# power_electronicsV4_1.net
KiCad netlist of a schematic drawn in EAGLE
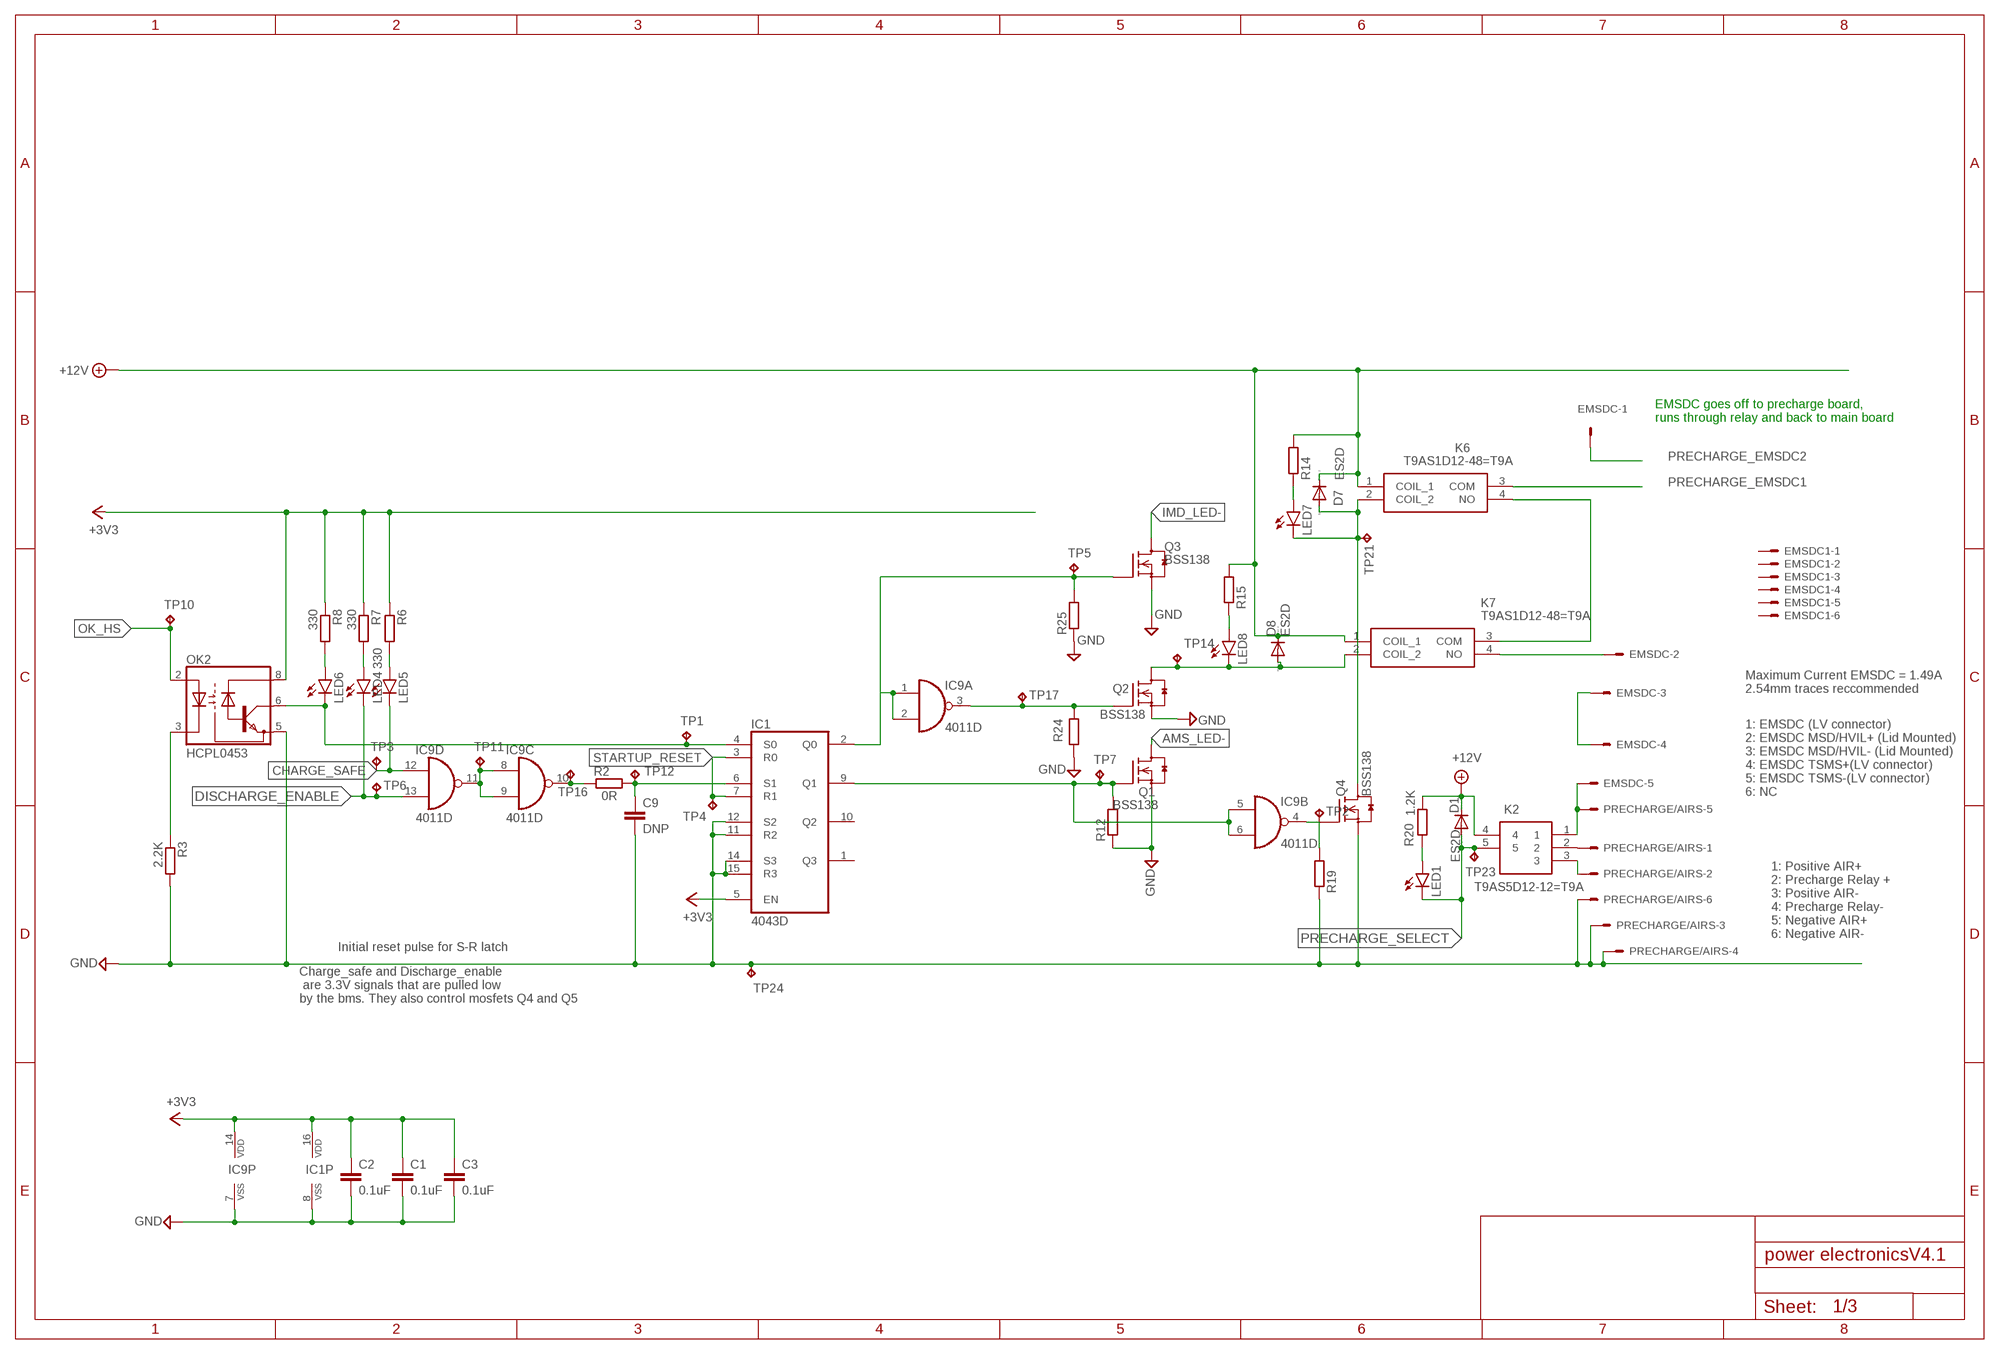
[diagram p0: schematic, sheet 1]
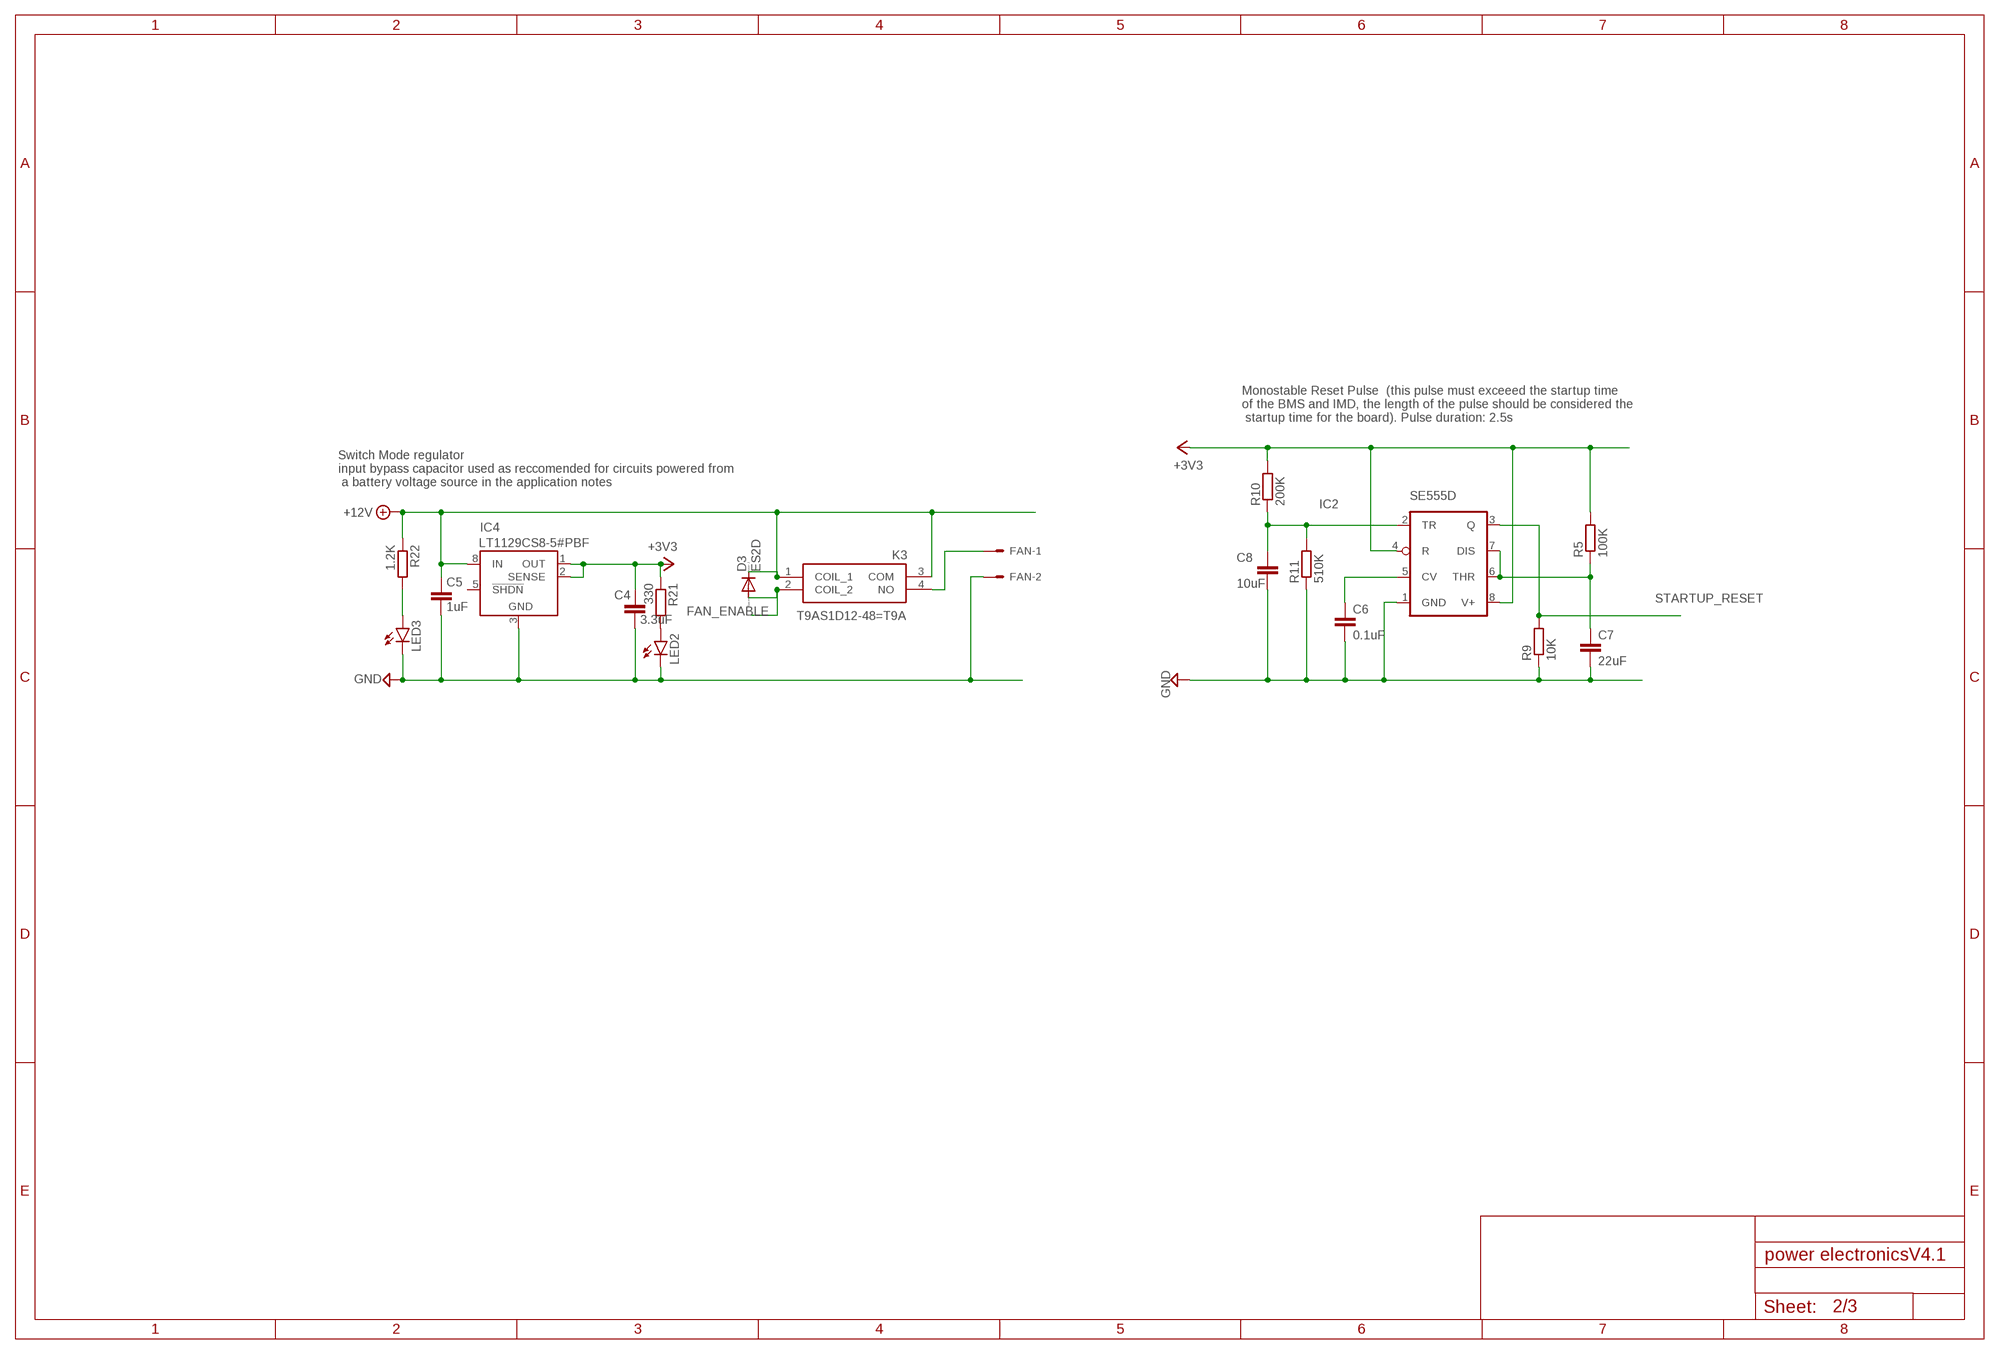
[diagram p1: schematic, sheet 2]
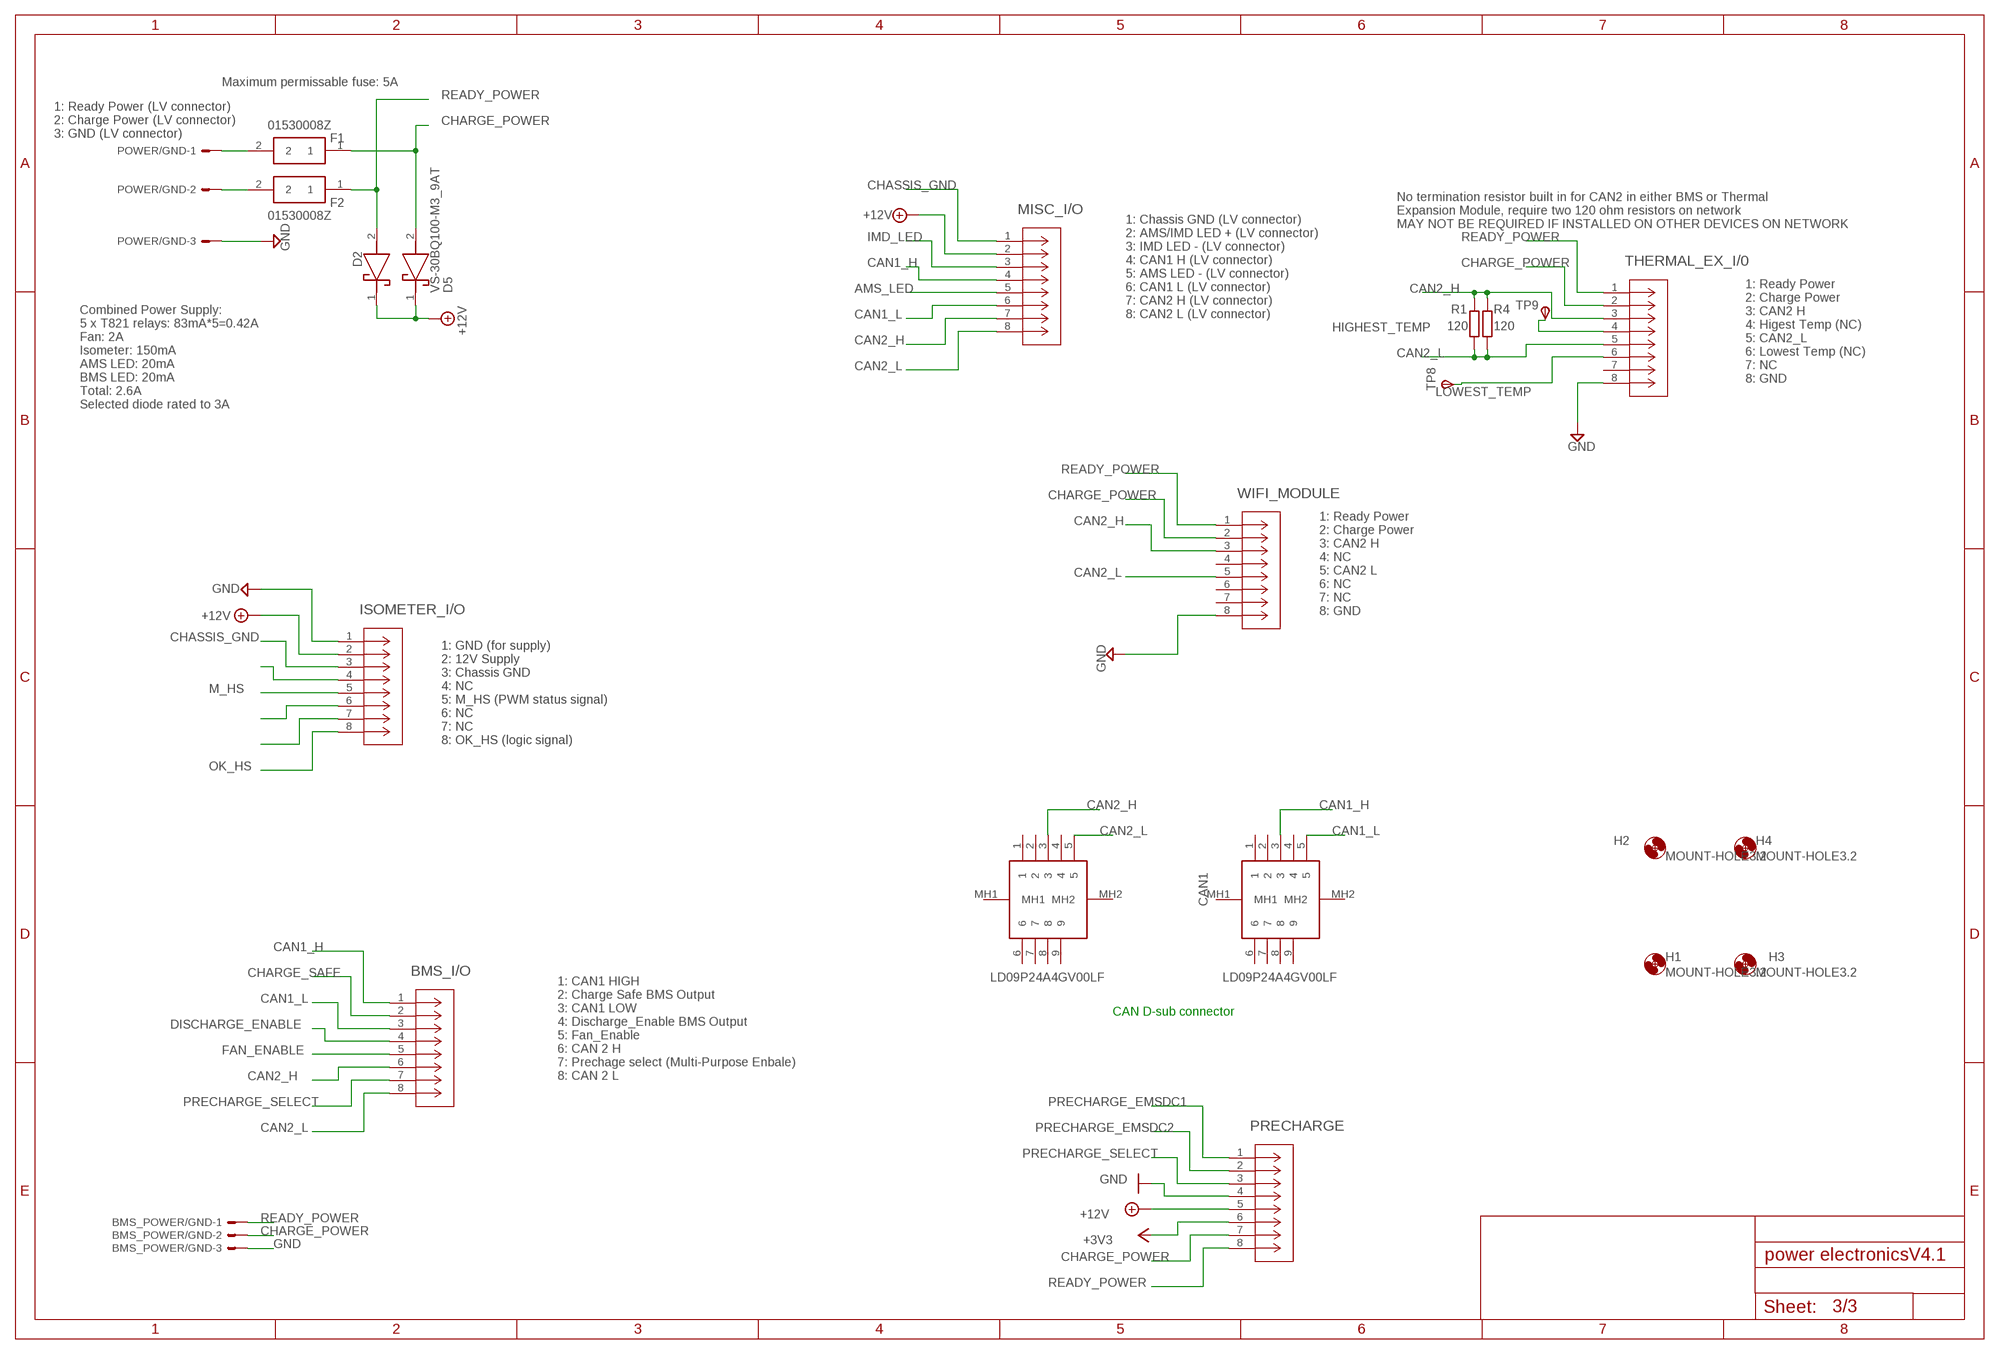
[diagram p2: schematic, sheet 3]

(export (version "E")
  (design (tool "Eeschema 10.0.6"))
  (components
    (comp (ref "BMS_I/O")
      (value "MINI-SPOX_22035085")
      (footprint "eagle-import:CON_22035085_MOL")
      (fields
        (field (name "MANUFACTURER_PART_NUMBER") "22035085")
        (field (name "COPYRIGHT") "Copyright (C) 2023 Ultra Librarian. All rights reserved.")
      )
      (libsource (lib "eagle-import") (part "MINI-SPOX_22035085"))
    )
    (comp (ref "BMS_POWER/GND")
      (value "KK-156-3")
      (footprint "eagle-import:KK-156-3")
      (fields (field (name "MF") "MOLEX"))
      (libsource (lib "eagle-import") (part "KK-156-3"))
    )
    (comp (ref "CAN1")
      (value "LD09P24A4GV00LF")
      (footprint "eagle-import:LD09P24A4GV00LF")
      (fields (field (name "MOUSER_PART_NUMBER") "649-LD09P24A4GV00LF"))
      (libsource (lib "eagle-import") (part "LD09P24A4GV00LF"))
    )
    (comp (ref "CAN2")
      (value "LD09P24A4GV00LF")
      (footprint "eagle-import:LD09P24A4GV00LF")
      (fields (field (name "MOUSER_PART_NUMBER") "649-LD09P24A4GV00LF"))
      (libsource (lib "eagle-import") (part "LD09P24A4GV00LF"))
    )
    (comp (ref "D2")
      (value "VS-30BQ100-M3_9AT")
      (footprint "eagle-import:DIOM7959X262N")
      (fields
        (field (name "MANUFACTURER_PART_NUMBER") "VS-30BQ100-M3/9AT")
        (field (name "MOUSER_PART_NUMBER") "78-VS-30BQ100-M39AT")
      )
      (libsource (lib "eagle-import") (part "VS-30BQ100-M3_9AT"))
    )
    (comp (ref "D5")
      (value "VS-30BQ100-M3_9AT")
      (footprint "eagle-import:DIOM7959X262N")
      (fields
        (field (name "MANUFACTURER_PART_NUMBER") "VS-30BQ100-M3/9AT")
        (field (name "MOUSER_PART_NUMBER") "78-VS-30BQ100-M39AT")
      )
      (libsource (lib "eagle-import") (part "VS-30BQ100-M3_9AT"))
    )
    (comp (ref "F1")
      (value "01530008Z")
      (footprint "eagle-import:01530008")
      (fields (field (name "RS_PART_NUMBER") "3607317"))
      (libsource (lib "eagle-import") (part "01530008Z"))
    )
    (comp (ref "F2")
      (value "01530008Z")
      (footprint "eagle-import:01530008")
      (fields (field (name "RS_PART_NUMBER") "3607317"))
      (libsource (lib "eagle-import") (part "01530008Z"))
    )
    (comp (ref "H1")
      (value "MOUNT-HOLE3.2")
      (footprint "eagle-import:3,2")
      (libsource (lib "eagle-import") (part "MOUNT-HOLE3.2"))
    )
    (comp (ref "H2")
      (value "MOUNT-HOLE3.2")
      (footprint "eagle-import:3,2")
      (libsource (lib "eagle-import") (part "MOUNT-HOLE3.2"))
    )
    (comp (ref "H3")
      (value "MOUNT-HOLE3.2")
      (footprint "eagle-import:3,2")
      (libsource (lib "eagle-import") (part "MOUNT-HOLE3.2"))
    )
    (comp (ref "H4")
      (value "MOUNT-HOLE3.2")
      (footprint "eagle-import:3,2")
      (libsource (lib "eagle-import") (part "MOUNT-HOLE3.2"))
    )
    (comp (ref "ISOMETER_I/O")
      (value "MINI-SPOX_22035085")
      (footprint "eagle-import:CON_22035085_MOL")
      (fields
        (field (name "MANUFACTURER_PART_NUMBER") "22035085")
        (field (name "COPYRIGHT") "Copyright (C) 2023 Ultra Librarian. All rights reserved.")
      )
      (libsource (lib "eagle-import") (part "MINI-SPOX_22035085"))
    )
    (comp (ref "MISC_I/O")
      (value "MINI-SPOX_22035085")
      (footprint "eagle-import:CON_22035085_MOL")
      (fields
        (field (name "MANUFACTURER_PART_NUMBER") "22035085")
        (field (name "COPYRIGHT") "Copyright (C) 2023 Ultra Librarian. All rights reserved.")
      )
      (libsource (lib "eagle-import") (part "MINI-SPOX_22035085"))
    )
    (comp (ref "POWER/GND")
      (value "KK-156-3")
      (footprint "eagle-import:KK-156-3")
      (fields (field (name "MF") "MOLEX"))
      (libsource (lib "eagle-import") (part "KK-156-3"))
    )
    (comp (ref "PRECHARGE")
      (value "MINI-SPOX_22035085")
      (footprint "eagle-import:CON_22035085_MOL")
      (fields
        (field (name "MANUFACTURER_PART_NUMBER") "22035085")
        (field (name "COPYRIGHT") "Copyright (C) 2023 Ultra Librarian. All rights reserved.")
      )
      (libsource (lib "eagle-import") (part "MINI-SPOX_22035085"))
    )
    (comp (ref "R1")
      (value "120")
      (footprint "eagle-import:R1206")
      (libsource (lib "eagle-import") (part "R-EU_R1206"))
    )
    (comp (ref "R4")
      (value "120")
      (footprint "eagle-import:R1206")
      (libsource (lib "eagle-import") (part "R-EU_R1206"))
    )
    (comp (ref "THERMAL_EX_I/0")
      (value "MINI-SPOX_22035085")
      (footprint "eagle-import:CON_22035085_MOL")
      (fields
        (field (name "MANUFACTURER_PART_NUMBER") "22035085")
        (field (name "COPYRIGHT") "Copyright (C) 2023 Ultra Librarian. All rights reserved.")
      )
      (libsource (lib "eagle-import") (part "MINI-SPOX_22035085"))
    )
    (comp (ref "TP8")
      (value "TPSTP11R")
      (footprint "eagle-import:TP11R")
      (libsource (lib "eagle-import") (part "TPSTP11R"))
    )
    (comp (ref "TP9")
      (value "TPSTP11R")
      (footprint "eagle-import:TP11R")
      (libsource (lib "eagle-import") (part "TPSTP11R"))
    )
    (comp (ref "WIFI_MODULE")
      (value "MINI-SPOX_22035085")
      (footprint "eagle-import:CON_22035085_MOL")
      (fields
        (field (name "MANUFACTURER_PART_NUMBER") "22035085")
        (field (name "COPYRIGHT") "Copyright (C) 2023 Ultra Librarian. All rights reserved.")
      )
      (libsource (lib "eagle-import") (part "MINI-SPOX_22035085"))
    )
    (comp (ref "C4")
      (value "3.3uF")
      (footprint "eagle-import:C0805")
      (libsource (lib "eagle-import") (part "C-EUC0805"))
    )
    (comp (ref "C5")
      (value "1uF")
      (footprint "eagle-import:C0805")
      (libsource (lib "eagle-import") (part "C-EUC0805"))
    )
    (comp (ref "C6")
      (value "0.1uF")
      (footprint "eagle-import:C0805")
      (libsource (lib "eagle-import") (part "C-EUC0805"))
    )
    (comp (ref "C7")
      (value "22uF")
      (footprint "eagle-import:C1206")
      (libsource (lib "eagle-import") (part "C-EUC1206"))
    )
    (comp (ref "C8")
      (value "10uF")
      (footprint "eagle-import:C0805")
      (libsource (lib "eagle-import") (part "C-EUC0805"))
    )
    (comp (ref "D3")
      (value "ES2D")
      (footprint "eagle-import:SMB")
      (libsource (lib "eagle-import") (part "ES2D"))
    )
    (comp (ref "FAN")
      (value "KK-156-2")
      (footprint "eagle-import:KK-156-2")
      (fields (field (name "MF") "MOLEX"))
      (libsource (lib "eagle-import") (part "KK-156-2"))
    )
    (comp (ref "IC2")
      (value "SE555D")
      (footprint "eagle-import:SO08")
      (libsource (lib "eagle-import") (part "555DSE"))
    )
    (comp (ref "IC4")
      (value "LT1129CS8")
      (footprint "eagle-import:SOIC8")
      (fields (field (name "MPN") "LT1129CS8-5#PBF"))
      (libsource (lib "eagle-import") (part "LT1129CS8"))
    )
    (comp (ref "K3")
      (value "T9AS1D12-48=T9A")
      (footprint "eagle-import:T9AS1D1248T9A")
      (fields (field (name "RS_PART_NUMBER") "6802534P"))
      (libsource (lib "eagle-import") (part "T9AS1D12-48=T9A"))
    )
    (comp (ref "LED2")
      (value "LEDSML0805")
      (footprint "eagle-import:SML0805")
      (libsource (lib "eagle-import") (part "LEDSML0805"))
    )
    (comp (ref "LED3")
      (value "LEDSML0805")
      (footprint "eagle-import:SML0805")
      (libsource (lib "eagle-import") (part "LEDSML0805"))
    )
    (comp (ref "R5")
      (value "100K")
      (footprint "eagle-import:R0805")
      (libsource (lib "eagle-import") (part "R-EU_R0805"))
    )
    (comp (ref "R9")
      (value "10K")
      (footprint "eagle-import:R0805")
      (libsource (lib "eagle-import") (part "R-EU_R0805"))
    )
    (comp (ref "R10")
      (value "200K")
      (footprint "eagle-import:R0805")
      (libsource (lib "eagle-import") (part "R-EU_R0805"))
    )
    (comp (ref "R11")
      (value "510K")
      (footprint "eagle-import:R0805")
      (libsource (lib "eagle-import") (part "R-EU_R0805"))
    )
    (comp (ref "R21")
      (value "330")
      (footprint "eagle-import:R0805")
      (libsource (lib "eagle-import") (part "R-EU_R0805"))
    )
    (comp (ref "R22")
      (value "1.2K")
      (footprint "eagle-import:R0805")
      (libsource (lib "eagle-import") (part "R-EU_R0805"))
    )
    (comp (ref "C1")
      (value "0.1uF")
      (footprint "eagle-import:C0805")
      (libsource (lib "eagle-import") (part "C-EUC0805"))
    )
    (comp (ref "C2")
      (value "0.1uF")
      (footprint "eagle-import:C0805")
      (libsource (lib "eagle-import") (part "C-EUC0805"))
    )
    (comp (ref "C3")
      (value "0.1uF")
      (footprint "eagle-import:C0805")
      (libsource (lib "eagle-import") (part "C-EUC0805"))
    )
    (comp (ref "C9")
      (value "DNP")
      (footprint "eagle-import:C0805K")
      (libsource (lib "eagle-import") (part "C-EUC0805K"))
    )
    (comp (ref "D1")
      (value "ES2D")
      (footprint "eagle-import:SMB")
      (libsource (lib "eagle-import") (part "ES2D"))
    )
    (comp (ref "D7")
      (value "ES2D")
      (footprint "eagle-import:SMB")
      (libsource (lib "eagle-import") (part "ES2D"))
    )
    (comp (ref "D8")
      (value "ES2D")
      (footprint "eagle-import:SMB")
      (libsource (lib "eagle-import") (part "ES2D"))
    )
    (comp (ref "EMSDC")
      (value "KK-156-6")
      (footprint "eagle-import:KK-156-6")
      (fields (field (name "MF") "MOLEX"))
      (libsource (lib "eagle-import") (part "KK-156-6"))
    )
    (comp (ref "EMSDC1")
      (value "KK-156-6")
      (footprint "eagle-import:KK-156-6")
      (fields (field (name "MF") "MOLEX"))
      (libsource (lib "eagle-import") (part "KK-156-6"))
    )
    (comp (ref "IC1")
      (value "4043D")
      (footprint "eagle-import:SO16")
      (libsource (lib "eagle-import") (part "4043D"))
    )
    (comp (ref "IC9")
      (value "4011D")
      (footprint "eagle-import:SO14")
      (libsource (lib "eagle-import") (part "4011D"))
    )
    (comp (ref "K2")
      (value "T9AS5D12-12=T9A")
      (footprint "eagle-import:T9AS1D12")
      (fields (field (name "RS_PART_NUMBER") "6802528"))
      (libsource (lib "eagle-import") (part "T9AS5D12-12=T9A"))
    )
    (comp (ref "K6")
      (value "T9AS1D12-48=T9A")
      (footprint "eagle-import:T9AS1D1248T9A")
      (libsource (lib "eagle-import") (part "T9AS1D12-12=T9A_T9AS1D12-48=T9A"))
    )
    (comp (ref "K7")
      (value "T9AS1D12-48=T9A")
      (footprint "eagle-import:T9AS1D1248T9A")
      (libsource (lib "eagle-import") (part "T9AS1D12-12=T9A_T9AS1D12-48=T9A"))
    )
    (comp (ref "LED1")
      (value "LEDSML0805")
      (footprint "eagle-import:SML0805")
      (libsource (lib "eagle-import") (part "LEDSML0805"))
    )
    (comp (ref "LED4")
      (value "LEDSML0805")
      (footprint "eagle-import:SML0805")
      (libsource (lib "eagle-import") (part "LEDSML0805"))
    )
    (comp (ref "LED5")
      (value "LEDSML0805")
      (footprint "eagle-import:SML0805")
      (libsource (lib "eagle-import") (part "LEDSML0805"))
    )
    (comp (ref "LED6")
      (value "LEDSML0805")
      (footprint "eagle-import:SML0805")
      (libsource (lib "eagle-import") (part "LEDSML0805"))
    )
    (comp (ref "LED7")
      (value "LEDSML0805")
      (footprint "eagle-import:SML0805")
      (libsource (lib "eagle-import") (part "LEDSML0805"))
    )
    (comp (ref "LED8")
      (value "LEDSML0805")
      (footprint "eagle-import:SML0805")
      (libsource (lib "eagle-import") (part "LEDSML0805"))
    )
    (comp (ref "OK2")
      (value "HCPL0453")
      (footprint "eagle-import:SOIC08")
      (fields (field (name "MF") "AGILENT TECHNOLOGIES") (field (name "MPN") "HCPL-0453-000E"))
      (libsource (lib "eagle-import") (part "HCPL0453"))
    )
    (comp (ref "PRECHARGE/AIRS")
      (value "KK-156-6")
      (footprint "eagle-import:KK-156-6")
      (fields (field (name "MF") "MOLEX"))
      (libsource (lib "eagle-import") (part "KK-156-6"))
    )
    (comp (ref "Q1")
      (value "BSS138")
      (footprint "eagle-import:SOT23")
      (libsource (lib "eagle-import") (part "BSS138"))
    )
    (comp (ref "Q2")
      (value "BSS138")
      (footprint "eagle-import:SOT23")
      (libsource (lib "eagle-import") (part "BSS138"))
    )
    (comp (ref "Q3")
      (value "BSS138")
      (footprint "eagle-import:SOT23")
      (libsource (lib "eagle-import") (part "BSS138"))
    )
    (comp (ref "Q4")
      (value "BSS138")
      (footprint "eagle-import:SOT23")
      (libsource (lib "eagle-import") (part "BSS138"))
    )
    (comp (ref "R2")
      (value "0R")
      (footprint "eagle-import:R0805")
      (libsource (lib "eagle-import") (part "R-EU_R0805"))
    )
    (comp (ref "R3")
      (value "2.2K")
      (footprint "eagle-import:R0805")
      (libsource (lib "eagle-import") (part "R-EU_R0805"))
    )
    (comp (ref "R6")
      (value "330")
      (footprint "eagle-import:R0805")
      (libsource (lib "eagle-import") (part "R-EU_R0805"))
    )
    (comp (ref "R7")
      (value "330")
      (footprint "eagle-import:R0805")
      (libsource (lib "eagle-import") (part "R-EU_R0805"))
    )
    (comp (ref "R8")
      (value "330")
      (footprint "eagle-import:R0805")
      (libsource (lib "eagle-import") (part "R-EU_R0805"))
    )
    (comp (ref "R12")
      (value "R-EU_R0805")
      (footprint "eagle-import:R0805")
      (libsource (lib "eagle-import") (part "R-EU_R0805"))
    )
    (comp (ref "R14")
      (value "R-EU_R0805")
      (footprint "eagle-import:R0805")
      (libsource (lib "eagle-import") (part "R-EU_R0805"))
    )
    (comp (ref "R15")
      (value "R-EU_R0805")
      (footprint "eagle-import:R0805")
      (libsource (lib "eagle-import") (part "R-EU_R0805"))
    )
    (comp (ref "R19")
      (value "R-EU_R0805")
      (footprint "eagle-import:R0805")
      (libsource (lib "eagle-import") (part "R-EU_R0805"))
    )
    (comp (ref "R20")
      (value "1.2K")
      (footprint "eagle-import:R0805")
      (libsource (lib "eagle-import") (part "R-EU_R0805"))
    )
    (comp (ref "R24")
      (value "R-EU_R0805")
      (footprint "eagle-import:R0805")
      (libsource (lib "eagle-import") (part "R-EU_R0805"))
    )
    (comp (ref "R25")
      (value "R-EU_R0805")
      (footprint "eagle-import:R0805")
      (libsource (lib "eagle-import") (part "R-EU_R0805"))
    )
    (comp (ref "TP1")
      (value "TPPAD1-17")
      (footprint "eagle-import:P1-17")
      (libsource (lib "eagle-import") (part "TPPAD1-17"))
    )
    (comp (ref "TP2")
      (value "TPPAD1-17")
      (footprint "eagle-import:P1-17")
      (libsource (lib "eagle-import") (part "TPPAD1-17"))
    )
    (comp (ref "TP3")
      (value "TPPAD1-17")
      (footprint "eagle-import:P1-17")
      (libsource (lib "eagle-import") (part "TPPAD1-17"))
    )
    (comp (ref "TP4")
      (value "TPPAD1-17")
      (footprint "eagle-import:P1-17")
      (libsource (lib "eagle-import") (part "TPPAD1-17"))
    )
    (comp (ref "TP5")
      (value "TPPAD1-17")
      (footprint "eagle-import:P1-17")
      (libsource (lib "eagle-import") (part "TPPAD1-17"))
    )
    (comp (ref "TP6")
      (value "TPPAD1-17")
      (footprint "eagle-import:P1-17")
      (libsource (lib "eagle-import") (part "TPPAD1-17"))
    )
    (comp (ref "TP7")
      (value "TPPAD1-17")
      (footprint "eagle-import:P1-17")
      (libsource (lib "eagle-import") (part "TPPAD1-17"))
    )
    (comp (ref "TP10")
      (value "TPPAD1-17")
      (footprint "eagle-import:P1-17")
      (libsource (lib "eagle-import") (part "TPPAD1-17"))
    )
    (comp (ref "TP11")
      (value "TPPAD1-17")
      (footprint "eagle-import:P1-17")
      (libsource (lib "eagle-import") (part "TPPAD1-17"))
    )
    (comp (ref "TP12")
      (value "TPPAD1-17")
      (footprint "eagle-import:P1-17")
      (libsource (lib "eagle-import") (part "TPPAD1-17"))
    )
    (comp (ref "TP14")
      (value "TPPAD1-17")
      (footprint "eagle-import:P1-17")
      (libsource (lib "eagle-import") (part "TPPAD1-17"))
    )
    (comp (ref "TP16")
      (value "TPPAD1-17")
      (footprint "eagle-import:P1-17")
      (libsource (lib "eagle-import") (part "TPPAD1-17"))
    )
    (comp (ref "TP17")
      (value "TPPAD1-17")
      (footprint "eagle-import:P1-17")
      (libsource (lib "eagle-import") (part "TPPAD1-17"))
    )
    (comp (ref "TP21")
      (value "TPPAD1-17")
      (footprint "eagle-import:P1-17")
      (libsource (lib "eagle-import") (part "TPPAD1-17"))
    )
    (comp (ref "TP23")
      (value "TPPAD1-17")
      (footprint "eagle-import:P1-17")
      (libsource (lib "eagle-import") (part "TPPAD1-17"))
    )
    (comp (ref "TP24")
      (value "TPPAD1-17")
      (footprint "eagle-import:P1-17")
      (libsource (lib "eagle-import") (part "TPPAD1-17"))
    )
  )
  (nets
    (net (code "1") (name "+3V3") (class "Default")
      (node (ref "C1") (pin "1") (pinfunction "1_1") (pintype "passive"))
      (node (ref "C2") (pin "1") (pinfunction "1_1") (pintype "passive"))
      (node (ref "C3") (pin "1") (pinfunction "1_1") (pintype "passive"))
      (node (ref "C4") (pin "1") (pinfunction "1_1") (pintype "passive"))
      (node (ref "IC1") (pin "16") (pinfunction "VDD_16") (pintype "power_in"))
      (node (ref "IC1") (pin "5") (pinfunction "EN_5") (pintype "input"))
      (node (ref "IC2") (pin "4") (pinfunction "R_4") (pintype "input"))
      (node (ref "IC2") (pin "8") (pinfunction "V+_8") (pintype "power_in"))
      (node (ref "IC4") (pin "1") (pinfunction "OUT_1") (pintype "output"))
      (node (ref "IC4") (pin "2") (pinfunction "SENSE_2") (pintype "input"))
      (node (ref "IC9") (pin "14") (pinfunction "VDD_14") (pintype "power_in"))
      (node (ref "OK2") (pin "8") (pinfunction "VCC_8") (pintype "passive"))
      (node (ref "PRECHARGE") (pin "6") (pinfunction "6_6") (pintype "passive"))
      (node (ref "R10") (pin "2") (pinfunction "2_2") (pintype "passive"))
      (node (ref "R21") (pin "1") (pinfunction "1_1") (pintype "passive"))
      (node (ref "R5") (pin "2") (pinfunction "2_2") (pintype "passive"))
      (node (ref "R6") (pin "1") (pinfunction "1_1") (pintype "passive"))
      (node (ref "R7") (pin "1") (pinfunction "1_1") (pintype "passive"))
      (node (ref "R8") (pin "1") (pinfunction "1_1") (pintype "passive"))
    )
    (net (code "2") (name "+12V") (class "Default")
      (node (ref "C5") (pin "1") (pinfunction "1_1") (pintype "passive"))
      (node (ref "D1") (pin "C") (pinfunction "C_C") (pintype "passive"))
      (node (ref "D2") (pin "1") (pinfunction "K_1") (pintype "bidirectional"))
      (node (ref "D3") (pin "C") (pinfunction "C_C") (pintype "passive"))
      (node (ref "D5") (pin "1") (pinfunction "K_1") (pintype "bidirectional"))
      (node (ref "D7") (pin "C") (pinfunction "C_C") (pintype "passive"))
      (node (ref "D8") (pin "C") (pinfunction "C_C") (pintype "passive"))
      (node (ref "IC4") (pin "8") (pinfunction "IN_8") (pintype "input"))
      (node (ref "ISOMETER_I/O") (pin "2") (pinfunction "2_2") (pintype "passive"))
      (node (ref "K2") (pin "4") (pinfunction "4_4") (pintype "bidirectional"))
      (node (ref "K3") (pin "1") (pinfunction "COIL_1_1") (pintype "bidirectional"))
      (node (ref "K3") (pin "3") (pinfunction "COM_3") (pintype "bidirectional"))
      (node (ref "K6") (pin "1") (pinfunction "COIL_1_1") (pintype "bidirectional"))
      (node (ref "K7") (pin "1") (pinfunction "COIL_1_1") (pintype "bidirectional"))
      (node (ref "MISC_I/O") (pin "2") (pinfunction "2_2") (pintype "passive"))
      (node (ref "PRECHARGE") (pin "5") (pinfunction "5_5") (pintype "passive"))
      (node (ref "R14") (pin "2") (pinfunction "2_2") (pintype "passive"))
      (node (ref "R15") (pin "2") (pinfunction "2_2") (pintype "passive"))
      (node (ref "R20") (pin "1") (pinfunction "1_1") (pintype "passive"))
      (node (ref "R22") (pin "1") (pinfunction "1_1") (pintype "passive"))
    )
    (net (code "3") (name "AMS_LED") (class "Default")
      (node (ref "MISC_I/O") (pin "5") (pinfunction "5_5") (pintype "passive"))
    )
    (net (code "4") (name "AMS_LED-") (class "Default")
      (node (ref "Q1") (pin "3") (pinfunction "D_3") (pintype "passive"))
    )
    (net (code "5") (name "CAN1_H") (class "Default")
      (node (ref "BMS_I/O") (pin "1") (pinfunction "1_1") (pintype "passive"))
      (node (ref "CAN1") (pin "3") (pinfunction "3_3") (pintype "bidirectional"))
      (node (ref "MISC_I/O") (pin "4") (pinfunction "4_4") (pintype "passive"))
    )
    (net (code "6") (name "CAN1_L") (class "Default")
      (node (ref "BMS_I/O") (pin "3") (pinfunction "3_3") (pintype "passive"))
      (node (ref "CAN1") (pin "5") (pinfunction "5_5") (pintype "bidirectional"))
      (node (ref "MISC_I/O") (pin "6") (pinfunction "6_6") (pintype "passive"))
    )
    (net (code "7") (name "CAN2_H") (class "Default")
      (node (ref "BMS_I/O") (pin "6") (pinfunction "6_6") (pintype "passive"))
      (node (ref "CAN2") (pin "3") (pinfunction "3_3") (pintype "bidirectional"))
      (node (ref "MISC_I/O") (pin "7") (pinfunction "7_7") (pintype "passive"))
      (node (ref "R1") (pin "1") (pinfunction "1_1") (pintype "passive"))
      (node (ref "R4") (pin "1") (pinfunction "1_1") (pintype "passive"))
      (node (ref "THERMAL_EX_I/0") (pin "3") (pinfunction "3_3") (pintype "passive"))
      (node (ref "WIFI_MODULE") (pin "3") (pinfunction "3_3") (pintype "passive"))
    )
    (net (code "8") (name "CAN2_L") (class "Default")
      (node (ref "BMS_I/O") (pin "8") (pinfunction "8_8") (pintype "passive"))
      (node (ref "CAN2") (pin "5") (pinfunction "5_5") (pintype "bidirectional"))
      (node (ref "MISC_I/O") (pin "8") (pinfunction "8_8") (pintype "passive"))
      (node (ref "R1") (pin "2") (pinfunction "2_2") (pintype "passive"))
      (node (ref "R4") (pin "2") (pinfunction "2_2") (pintype "passive"))
      (node (ref "THERMAL_EX_I/0") (pin "5") (pinfunction "5_5") (pintype "passive"))
      (node (ref "WIFI_MODULE") (pin "5") (pinfunction "5_5") (pintype "passive"))
    )
    (net (code "9") (name "CHARGE_POWER") (class "Default")
      (node (ref "BMS_POWER/GND") (pin "2") (pinfunction "S_2") (pintype "passive"))
      (node (ref "D5") (pin "2") (pinfunction "A_2") (pintype "bidirectional"))
      (node (ref "F1") (pin "1") (pinfunction "1_1") (pintype "bidirectional"))
      (node (ref "PRECHARGE") (pin "7") (pinfunction "7_7") (pintype "passive"))
      (node (ref "THERMAL_EX_I/0") (pin "2") (pinfunction "2_2") (pintype "passive"))
      (node (ref "WIFI_MODULE") (pin "2") (pinfunction "2_2") (pintype "passive"))
    )
    (net (code "10") (name "CHARGE_SAFE") (class "Default")
      (node (ref "BMS_I/O") (pin "2") (pinfunction "2_2") (pintype "passive"))
      (node (ref "IC9") (pin "12") (pinfunction "I0_12") (pintype "input"))
      (node (ref "LED5") (pin "C") (pinfunction "C_C") (pintype "passive"))
      (node (ref "TP3") (pin "TP") (pinfunction "TP_TP") (pintype "input"))
    )
    (net (code "11") (name "CHASSIS_GND") (class "Default")
      (node (ref "ISOMETER_I/O") (pin "3") (pinfunction "3_3") (pintype "passive"))
      (node (ref "MISC_I/O") (pin "1") (pinfunction "1_1") (pintype "passive"))
    )
    (net (code "12") (name "DISCHARGE_ENABLE") (class "Default")
      (node (ref "BMS_I/O") (pin "4") (pinfunction "4_4") (pintype "passive"))
      (node (ref "IC1") (pin "9") (pinfunction "Q1_9") (pintype "output"))
      (node (ref "IC9") (pin "13") (pinfunction "I1_13") (pintype "input"))
      (node (ref "IC9") (pin "5") (pinfunction "I0_5") (pintype "input"))
      (node (ref "IC9") (pin "6") (pinfunction "I1_6") (pintype "input"))
      (node (ref "LED4") (pin "C") (pinfunction "C_C") (pintype "passive"))
      (node (ref "Q1") (pin "1") (pinfunction "G_1") (pintype "passive"))
      (node (ref "R12") (pin "2") (pinfunction "2_2") (pintype "passive"))
      (node (ref "TP6") (pin "TP") (pinfunction "TP_TP") (pintype "input"))
      (node (ref "TP7") (pin "TP") (pinfunction "TP_TP") (pintype "input"))
    )
    (net (code "13") (name "FAN_ENABLE") (class "Default")
      (node (ref "BMS_I/O") (pin "5") (pinfunction "5_5") (pintype "passive"))
      (node (ref "D3") (pin "A") (pinfunction "A_A") (pintype "passive"))
      (node (ref "K3") (pin "2") (pinfunction "COIL_2_2") (pintype "bidirectional"))
    )
    (net (code "14") (name "GND") (class "Default")
      (node (ref "BMS_POWER/GND") (pin "3") (pinfunction "S_3") (pintype "passive"))
      (node (ref "C1") (pin "2") (pinfunction "2_2") (pintype "passive"))
      (node (ref "C2") (pin "2") (pinfunction "2_2") (pintype "passive"))
      (node (ref "C3") (pin "2") (pinfunction "2_2") (pintype "passive"))
      (node (ref "C4") (pin "2") (pinfunction "2_2") (pintype "passive"))
      (node (ref "C5") (pin "2") (pinfunction "2_2") (pintype "passive"))
      (node (ref "C6") (pin "2") (pinfunction "2_2") (pintype "passive"))
      (node (ref "C7") (pin "2") (pinfunction "2_2") (pintype "passive"))
      (node (ref "C8") (pin "2") (pinfunction "2_2") (pintype "passive"))
      (node (ref "C9") (pin "2") (pinfunction "2_2") (pintype "passive"))
      (node (ref "FAN") (pin "2") (pinfunction "S_2") (pintype "passive"))
      (node (ref "IC1") (pin "11") (pinfunction "R2_11") (pintype "input"))
      (node (ref "IC1") (pin "12") (pinfunction "S2_12") (pintype "input"))
      (node (ref "IC1") (pin "14") (pinfunction "S3_14") (pintype "input"))
      (node (ref "IC1") (pin "15") (pinfunction "R3_15") (pintype "input"))
      (node (ref "IC1") (pin "8") (pinfunction "VSS_8") (pintype "power_in"))
      (node (ref "IC2") (pin "1") (pinfunction "GND_1") (pintype "power_in"))
      (node (ref "IC4") (pin "3") (pinfunction "GND_3") (pintype "power_in"))
      (node (ref "IC9") (pin "7") (pinfunction "VSS_7") (pintype "power_in"))
      (node (ref "ISOMETER_I/O") (pin "1") (pinfunction "1_1") (pintype "passive"))
      (node (ref "LED2") (pin "C") (pinfunction "C_C") (pintype "passive"))
      (node (ref "LED3") (pin "C") (pinfunction "C_C") (pintype "passive"))
      (node (ref "OK2") (pin "5") (pinfunction "GND_5") (pintype "passive"))
      (node (ref "POWER/GND") (pin "3") (pinfunction "S_3") (pintype "passive"))
      (node (ref "PRECHARGE") (pin "4") (pinfunction "4_4") (pintype "passive"))
      (node (ref "PRECHARGE/AIRS") (pin "3") (pinfunction "S_3") (pintype "passive"))
      (node (ref "PRECHARGE/AIRS") (pin "4") (pinfunction "S_4") (pintype "passive"))
      (node (ref "PRECHARGE/AIRS") (pin "6") (pinfunction "S_6") (pintype "passive"))
      (node (ref "Q1") (pin "2") (pinfunction "S_2") (pintype "passive"))
      (node (ref "Q2") (pin "2") (pinfunction "S_2") (pintype "passive"))
      (node (ref "Q3") (pin "2") (pinfunction "S_2") (pintype "passive"))
      (node (ref "Q4") (pin "2") (pinfunction "S_2") (pintype "passive"))
      (node (ref "R11") (pin "1") (pinfunction "1_1") (pintype "passive"))
      (node (ref "R12") (pin "1") (pinfunction "1_1") (pintype "passive"))
      (node (ref "R19") (pin "1") (pinfunction "1_1") (pintype "passive"))
      (node (ref "R24") (pin "1") (pinfunction "1_1") (pintype "passive"))
      (node (ref "R25") (pin "1") (pinfunction "1_1") (pintype "passive"))
      (node (ref "R3") (pin "2") (pinfunction "2_2") (pintype "passive"))
      (node (ref "R9") (pin "1") (pinfunction "1_1") (pintype "passive"))
      (node (ref "THERMAL_EX_I/0") (pin "8") (pinfunction "8_8") (pintype "passive"))
      (node (ref "TP24") (pin "TP") (pinfunction "TP_TP") (pintype "input"))
      (node (ref "WIFI_MODULE") (pin "8") (pinfunction "8_8") (pintype "passive"))
    )
    (net (code "15") (name "HIGHEST_TEMP") (class "Default")
      (node (ref "THERMAL_EX_I/0") (pin "4") (pinfunction "4_4") (pintype "passive"))
      (node (ref "TP9") (pin "TP") (pinfunction "PP_TP") (pintype "input"))
    )
    (net (code "16") (name "IMD_LED") (class "Default")
      (node (ref "MISC_I/O") (pin "3") (pinfunction "3_3") (pintype "passive"))
    )
    (net (code "17") (name "IMD_LED-") (class "Default")
      (node (ref "Q3") (pin "3") (pinfunction "D_3") (pintype "passive"))
    )
    (net (code "18") (name "LOWEST_TEMP") (class "Default")
      (node (ref "THERMAL_EX_I/0") (pin "6") (pinfunction "6_6") (pintype "passive"))
      (node (ref "TP8") (pin "TP") (pinfunction "PP_TP") (pintype "input"))
    )
    (net (code "19") (name "M_HS") (class "Default")
      (node (ref "ISOMETER_I/O") (pin "5") (pinfunction "5_5") (pintype "passive"))
    )
    (net (code "20") (name "Net-(EMSDCB-S)") (class "Default")
      (node (ref "EMSDC") (pin "2") (pinfunction "S_2") (pintype "passive"))
      (node (ref "K7") (pin "4") (pinfunction "NO_4") (pintype "bidirectional"))
    )
    (net (code "21") (name "Net-(EMSDCC-S)") (class "Default")
      (node (ref "EMSDC") (pin "3") (pinfunction "S_3") (pintype "passive"))
      (node (ref "EMSDC") (pin "4") (pinfunction "S_4") (pintype "passive"))
    )
    (net (code "22") (name "Net-(EMSDCE-S)") (class "Default")
      (node (ref "EMSDC") (pin "5") (pinfunction "S_5") (pintype "passive"))
      (node (ref "K2") (pin "1") (pinfunction "1_1") (pintype "bidirectional"))
      (node (ref "PRECHARGE/AIRS") (pin "5") (pinfunction "S_5") (pintype "passive"))
    )
    (net (code "23") (name "Net-(FANA-S)") (class "Default")
      (node (ref "FAN") (pin "1") (pinfunction "S_1") (pintype "passive"))
      (node (ref "K3") (pin "4") (pinfunction "NO_4") (pintype "bidirectional"))
    )
    (net (code "24") (name "Net-(IC1A-Q0)") (class "Default")
      (node (ref "IC1") (pin "2") (pinfunction "Q0_2") (pintype "output"))
      (node (ref "IC9") (pin "1") (pinfunction "I0_1") (pintype "input"))
      (node (ref "IC9") (pin "2") (pinfunction "I1_2") (pintype "input"))
      (node (ref "Q3") (pin "1") (pinfunction "G_1") (pintype "passive"))
      (node (ref "R25") (pin "2") (pinfunction "2_2") (pintype "passive"))
      (node (ref "TP5") (pin "TP") (pinfunction "TP_TP") (pintype "input"))
    )
    (net (code "25") (name "Net-(IC1A-S0)") (class "Default")
      (node (ref "IC1") (pin "4") (pinfunction "S0_4") (pintype "input"))
      (node (ref "LED6") (pin "C") (pinfunction "C_C") (pintype "passive"))
      (node (ref "OK2") (pin "6") (pinfunction "VO_6") (pintype "passive"))
      (node (ref "TP1") (pin "TP") (pinfunction "TP_TP") (pintype "input"))
    )
    (net (code "26") (name "Net-(IC1A-S1)") (class "Default")
      (node (ref "C9") (pin "1") (pinfunction "1_1") (pintype "passive"))
      (node (ref "IC1") (pin "6") (pinfunction "S1_6") (pintype "input"))
      (node (ref "R2") (pin "2") (pinfunction "2_2") (pintype "passive"))
      (node (ref "TP12") (pin "TP") (pinfunction "TP_TP") (pintype "input"))
    )
    (net (code "27") (name "Net-(IC2-CV)") (class "Default")
      (node (ref "C6") (pin "1") (pinfunction "1_1") (pintype "passive"))
      (node (ref "IC2") (pin "5") (pinfunction "CV_5") (pintype "input"))
    )
    (net (code "28") (name "Net-(IC2-DIS)") (class "Default")
      (node (ref "C7") (pin "1") (pinfunction "1_1") (pintype "passive"))
      (node (ref "IC2") (pin "6") (pinfunction "THR_6") (pintype "input"))
      (node (ref "IC2") (pin "7") (pinfunction "DIS_7") (pintype "input"))
      (node (ref "R5") (pin "1") (pinfunction "1_1") (pintype "passive"))
    )
    (net (code "29") (name "Net-(IC2-TR)") (class "Default")
      (node (ref "C8") (pin "1") (pinfunction "1_1") (pintype "passive"))
      (node (ref "IC2") (pin "2") (pinfunction "TR_2") (pintype "input"))
      (node (ref "R10") (pin "1") (pinfunction "1_1") (pintype "passive"))
      (node (ref "R11") (pin "2") (pinfunction "2_2") (pintype "passive"))
    )
    (net (code "30") (name "Net-(IC9A-O)") (class "Default")
      (node (ref "IC9") (pin "3") (pinfunction "O_3") (pintype "output"))
      (node (ref "Q2") (pin "1") (pinfunction "G_1") (pintype "passive"))
      (node (ref "R24") (pin "2") (pinfunction "2_2") (pintype "passive"))
      (node (ref "TP17") (pin "TP") (pinfunction "TP_TP") (pintype "input"))
    )
    (net (code "31") (name "Net-(IC9B-O)") (class "Default")
      (node (ref "IC9") (pin "4") (pinfunction "O_4") (pintype "output"))
      (node (ref "Q4") (pin "1") (pinfunction "G_1") (pintype "passive"))
      (node (ref "R19") (pin "2") (pinfunction "2_2") (pintype "passive"))
      (node (ref "TP2") (pin "TP") (pinfunction "TP_TP") (pintype "input"))
    )
    (net (code "32") (name "Net-(IC9C-I0)") (class "Default")
      (node (ref "IC9") (pin "11") (pinfunction "O_11") (pintype "output"))
      (node (ref "IC9") (pin "8") (pinfunction "I0_8") (pintype "input"))
      (node (ref "IC9") (pin "9") (pinfunction "I1_9") (pintype "input"))
      (node (ref "TP11") (pin "TP") (pinfunction "TP_TP") (pintype "input"))
    )
    (net (code "33") (name "Net-(IC9C-O)") (class "Default")
      (node (ref "IC9") (pin "10") (pinfunction "O_10") (pintype "output"))
      (node (ref "R2") (pin "1") (pinfunction "1_1") (pintype "passive"))
      (node (ref "TP16") (pin "TP") (pinfunction "TP_TP") (pintype "input"))
    )
    (net (code "34") (name "Net-(K6-COIL_2)") (class "Default")
      (node (ref "D7") (pin "A") (pinfunction "A_A") (pintype "passive"))
      (node (ref "K6") (pin "2") (pinfunction "COIL_2_2") (pintype "bidirectional"))
      (node (ref "LED7") (pin "C") (pinfunction "C_C") (pintype "passive"))
      (node (ref "Q4") (pin "3") (pinfunction "D_3") (pintype "passive"))
      (node (ref "TP21") (pin "TP") (pinfunction "TP_TP") (pintype "input"))
    )
    (net (code "35") (name "Net-(K6-NO)") (class "Default")
      (node (ref "K6") (pin "4") (pinfunction "NO_4") (pintype "bidirectional"))
      (node (ref "K7") (pin "3") (pinfunction "COM_3") (pintype "bidirectional"))
    )
    (net (code "36") (name "Net-(K7-COIL_2)") (class "Default")
      (node (ref "D8") (pin "A") (pinfunction "A_A") (pintype "passive"))
      (node (ref "K7") (pin "2") (pinfunction "COIL_2_2") (pintype "bidirectional"))
      (node (ref "LED8") (pin "C") (pinfunction "C_C") (pintype "passive"))
      (node (ref "Q2") (pin "3") (pinfunction "D_3") (pintype "passive"))
      (node (ref "TP14") (pin "TP") (pinfunction "TP_TP") (pintype "input"))
    )
    (net (code "37") (name "Net-(LED1-PadA)") (class "Default")
      (node (ref "LED1") (pin "A") (pinfunction "A_A") (pintype "passive"))
      (node (ref "R20") (pin "2") (pinfunction "2_2") (pintype "passive"))
    )
    (net (code "38") (name "Net-(LED2-PadA)") (class "Default")
      (node (ref "LED2") (pin "A") (pinfunction "A_A") (pintype "passive"))
      (node (ref "R21") (pin "2") (pinfunction "2_2") (pintype "passive"))
    )
    (net (code "39") (name "Net-(LED3-PadA)") (class "Default")
      (node (ref "LED3") (pin "A") (pinfunction "A_A") (pintype "passive"))
      (node (ref "R22") (pin "2") (pinfunction "2_2") (pintype "passive"))
    )
    (net (code "40") (name "Net-(LED4-PadA)") (class "Default")
      (node (ref "LED4") (pin "A") (pinfunction "A_A") (pintype "passive"))
      (node (ref "R7") (pin "2") (pinfunction "2_2") (pintype "passive"))
    )
    (net (code "41") (name "Net-(LED5-PadA)") (class "Default")
      (node (ref "LED5") (pin "A") (pinfunction "A_A") (pintype "passive"))
      (node (ref "R6") (pin "2") (pinfunction "2_2") (pintype "passive"))
    )
    (net (code "42") (name "Net-(LED6-PadA)") (class "Default")
      (node (ref "LED6") (pin "A") (pinfunction "A_A") (pintype "passive"))
      (node (ref "R8") (pin "2") (pinfunction "2_2") (pintype "passive"))
    )
    (net (code "43") (name "Net-(LED7-PadA)") (class "Default")
      (node (ref "LED7") (pin "A") (pinfunction "A_A") (pintype "passive"))
      (node (ref "R14") (pin "1") (pinfunction "1_1") (pintype "passive"))
    )
    (net (code "44") (name "Net-(LED8-PadA)") (class "Default")
      (node (ref "LED8") (pin "A") (pinfunction "A_A") (pintype "passive"))
      (node (ref "R15") (pin "1") (pinfunction "1_1") (pintype "passive"))
    )
    (net (code "45") (name "Net-(OK2-C)") (class "Default")
      (node (ref "OK2") (pin "3") (pinfunction "C_3") (pintype "passive"))
      (node (ref "R3") (pin "1") (pinfunction "1_1") (pintype "passive"))
    )
    (net (code "46") (name "Net-(POWER/GNDA-S)") (class "Default")
      (node (ref "F1") (pin "2") (pinfunction "2_2") (pintype "bidirectional"))
      (node (ref "POWER/GND") (pin "1") (pinfunction "S_1") (pintype "passive"))
    )
    (net (code "47") (name "Net-(POWER/GNDB-S)") (class "Default")
      (node (ref "F2") (pin "2") (pinfunction "2_2") (pintype "bidirectional"))
      (node (ref "POWER/GND") (pin "2") (pinfunction "S_2") (pintype "passive"))
    )
    (net (code "48") (name "Net-(PRECHARGE/AIRSA-S)") (class "Default")
      (node (ref "K2") (pin "2") (pinfunction "2_2") (pintype "bidirectional"))
      (node (ref "PRECHARGE/AIRS") (pin "1") (pinfunction "S_1") (pintype "passive"))
    )
    (net (code "49") (name "Net-(PRECHARGE/AIRSB-S)") (class "Default")
      (node (ref "K2") (pin "3") (pinfunction "3_3") (pintype "bidirectional"))
      (node (ref "PRECHARGE/AIRS") (pin "2") (pinfunction "S_2") (pintype "passive"))
    )
    (net (code "50") (name "OK_HS") (class "Default")
      (node (ref "ISOMETER_I/O") (pin "8") (pinfunction "8_8") (pintype "passive"))
      (node (ref "OK2") (pin "2") (pinfunction "A_2") (pintype "passive"))
      (node (ref "TP10") (pin "TP") (pinfunction "TP_TP") (pintype "input"))
    )
    (net (code "51") (name "PRECHARGE_EMSDC1") (class "Default")
      (node (ref "K6") (pin "3") (pinfunction "COM_3") (pintype "bidirectional"))
      (node (ref "PRECHARGE") (pin "1") (pinfunction "1_1") (pintype "passive"))
    )
    (net (code "52") (name "PRECHARGE_EMSDC2") (class "Default")
      (node (ref "EMSDC") (pin "1") (pinfunction "S_1") (pintype "passive"))
      (node (ref "PRECHARGE") (pin "2") (pinfunction "2_2") (pintype "passive"))
    )
    (net (code "53") (name "PRECHARGE_SELECT") (class "Default")
      (node (ref "BMS_I/O") (pin "7") (pinfunction "7_7") (pintype "passive"))
      (node (ref "D1") (pin "A") (pinfunction "A_A") (pintype "passive"))
      (node (ref "K2") (pin "5") (pinfunction "5_5") (pintype "bidirectional"))
      (node (ref "LED1") (pin "C") (pinfunction "C_C") (pintype "passive"))
      (node (ref "PRECHARGE") (pin "3") (pinfunction "3_3") (pintype "passive"))
      (node (ref "TP23") (pin "TP") (pinfunction "TP_TP") (pintype "input"))
    )
    (net (code "54") (name "READY_POWER") (class "Default")
      (node (ref "BMS_POWER/GND") (pin "1") (pinfunction "S_1") (pintype "passive"))
      (node (ref "D2") (pin "2") (pinfunction "A_2") (pintype "bidirectional"))
      (node (ref "F2") (pin "1") (pinfunction "1_1") (pintype "bidirectional"))
      (node (ref "PRECHARGE") (pin "8") (pinfunction "8_8") (pintype "passive"))
      (node (ref "THERMAL_EX_I/0") (pin "1") (pinfunction "1_1") (pintype "passive"))
      (node (ref "WIFI_MODULE") (pin "1") (pinfunction "1_1") (pintype "passive"))
    )
    (net (code "55") (name "STARTUP_RESET") (class "Default")
      (node (ref "IC1") (pin "3") (pinfunction "R0_3") (pintype "input"))
      (node (ref "IC1") (pin "7") (pinfunction "R1_7") (pintype "input"))
      (node (ref "IC2") (pin "3") (pinfunction "Q_3") (pintype "output"))
      (node (ref "R9") (pin "2") (pinfunction "2_2") (pintype "passive"))
      (node (ref "TP4") (pin "TP") (pinfunction "TP_TP") (pintype "input"))
    )
    (net (code "56") (name "unconnected-(CAN1-Pad1)") (class "Default")
      (node (ref "CAN1") (pin "1") (pinfunction "1_1") (pintype "bidirectional"))
    )
    (net (code "57") (name "unconnected-(CAN1-Pad2)") (class "Default")
      (node (ref "CAN1") (pin "2") (pinfunction "2_2") (pintype "bidirectional"))
    )
    (net (code "58") (name "unconnected-(CAN1-Pad4)") (class "Default")
      (node (ref "CAN1") (pin "4") (pinfunction "4_4") (pintype "bidirectional"))
    )
    (net (code "59") (name "unconnected-(CAN1-Pad6)") (class "Default")
      (node (ref "CAN1") (pin "6") (pinfunction "6_6") (pintype "bidirectional"))
    )
    (net (code "60") (name "unconnected-(CAN1-Pad7)") (class "Default")
      (node (ref "CAN1") (pin "7") (pinfunction "7_7") (pintype "bidirectional"))
    )
    (net (code "61") (name "unconnected-(CAN1-Pad8)") (class "Default")
      (node (ref "CAN1") (pin "8") (pinfunction "8_8") (pintype "bidirectional"))
    )
    (net (code "62") (name "unconnected-(CAN1-Pad9)") (class "Default")
      (node (ref "CAN1") (pin "9") (pinfunction "9_9") (pintype "bidirectional"))
    )
    (net (code "63") (name "unconnected-(CAN1-PadMH1)") (class "Default")
      (node (ref "CAN1") (pin "MH1") (pinfunction "MH1_MH1") (pintype "bidirectional"))
    )
    (net (code "64") (name "unconnected-(CAN1-PadMH2)") (class "Default")
      (node (ref "CAN1") (pin "MH2") (pinfunction "MH2_MH2") (pintype "bidirectional"))
    )
    (net (code "65") (name "unconnected-(CAN2-Pad1)") (class "Default")
      (node (ref "CAN2") (pin "1") (pinfunction "1_1") (pintype "bidirectional"))
    )
    (net (code "66") (name "unconnected-(CAN2-Pad2)") (class "Default")
      (node (ref "CAN2") (pin "2") (pinfunction "2_2") (pintype "bidirectional"))
    )
    (net (code "67") (name "unconnected-(CAN2-Pad4)") (class "Default")
      (node (ref "CAN2") (pin "4") (pinfunction "4_4") (pintype "bidirectional"))
    )
    (net (code "68") (name "unconnected-(CAN2-Pad6)") (class "Default")
      (node (ref "CAN2") (pin "6") (pinfunction "6_6") (pintype "bidirectional"))
    )
    (net (code "69") (name "unconnected-(CAN2-Pad7)") (class "Default")
      (node (ref "CAN2") (pin "7") (pinfunction "7_7") (pintype "bidirectional"))
    )
    (net (code "70") (name "unconnected-(CAN2-Pad8)") (class "Default")
      (node (ref "CAN2") (pin "8") (pinfunction "8_8") (pintype "bidirectional"))
    )
    (net (code "71") (name "unconnected-(CAN2-Pad9)") (class "Default")
      (node (ref "CAN2") (pin "9") (pinfunction "9_9") (pintype "bidirectional"))
    )
    (net (code "72") (name "unconnected-(CAN2-PadMH1)") (class "Default")
      (node (ref "CAN2") (pin "MH1") (pinfunction "MH1_MH1") (pintype "bidirectional"))
    )
    (net (code "73") (name "unconnected-(CAN2-PadMH2)") (class "Default")
      (node (ref "CAN2") (pin "MH2") (pinfunction "MH2_MH2") (pintype "bidirectional"))
    )
    (net (code "74") (name "unconnected-(EMSDC1A-S-Pad1)") (class "Default")
      (node (ref "EMSDC1") (pin "1") (pinfunction "S_1") (pintype "passive"))
    )
    (net (code "75") (name "unconnected-(EMSDC1B-S-Pad2)") (class "Default")
      (node (ref "EMSDC1") (pin "2") (pinfunction "S_2") (pintype "passive"))
    )
    (net (code "76") (name "unconnected-(EMSDC1C-S-Pad3)") (class "Default")
      (node (ref "EMSDC1") (pin "3") (pinfunction "S_3") (pintype "passive"))
    )
    (net (code "77") (name "unconnected-(EMSDC1D-S-Pad4)") (class "Default")
      (node (ref "EMSDC1") (pin "4") (pinfunction "S_4") (pintype "passive"))
    )
    (net (code "78") (name "unconnected-(EMSDC1E-S-Pad5)") (class "Default")
      (node (ref "EMSDC1") (pin "5") (pinfunction "S_5") (pintype "passive"))
    )
    (net (code "79") (name "unconnected-(EMSDC1F-S-Pad6)") (class "Default")
      (node (ref "EMSDC1") (pin "6") (pinfunction "S_6") (pintype "passive"))
    )
    (net (code "80") (name "unconnected-(IC1A-Q2-Pad10)") (class "Default")
      (node (ref "IC1") (pin "10") (pinfunction "Q2_10") (pintype "output"))
    )
    (net (code "81") (name "unconnected-(IC1A-Q3-Pad1)") (class "Default")
      (node (ref "IC1") (pin "1") (pinfunction "Q3_1") (pintype "output"))
    )
    (net (code "82") (name "unconnected-(IC4A-~{SHDN}-Pad5)") (class "Default")
      (node (ref "IC4") (pin "5") (pinfunction "~{SHDN}_5") (pintype "input"))
    )
    (net (code "83") (name "unconnected-(ISOMETER_I/O-Pad4)") (class "Default")
      (node (ref "ISOMETER_I/O") (pin "4") (pinfunction "4_4") (pintype "passive"))
    )
    (net (code "84") (name "unconnected-(ISOMETER_I/O-Pad6)") (class "Default")
      (node (ref "ISOMETER_I/O") (pin "6") (pinfunction "6_6") (pintype "passive"))
    )
    (net (code "85") (name "unconnected-(ISOMETER_I/O-Pad7)") (class "Default")
      (node (ref "ISOMETER_I/O") (pin "7") (pinfunction "7_7") (pintype "passive"))
    )
    (net (code "86") (name "unconnected-(THERMAL_EX_I/0-Pad7)") (class "Default")
      (node (ref "THERMAL_EX_I/0") (pin "7") (pinfunction "7_7") (pintype "passive"))
    )
    (net (code "87") (name "unconnected-(WIFI_MODULE-Pad4)") (class "Default")
      (node (ref "WIFI_MODULE") (pin "4") (pinfunction "4_4") (pintype "passive"))
    )
    (net (code "88") (name "unconnected-(WIFI_MODULE-Pad6)") (class "Default")
      (node (ref "WIFI_MODULE") (pin "6") (pinfunction "6_6") (pintype "passive"))
    )
    (net (code "89") (name "unconnected-(WIFI_MODULE-Pad7)") (class "Default")
      (node (ref "WIFI_MODULE") (pin "7") (pinfunction "7_7") (pintype "passive"))
    )
  )
)
